# m2_old.net
KiCad netlist of a schematic drawn in EAGLE
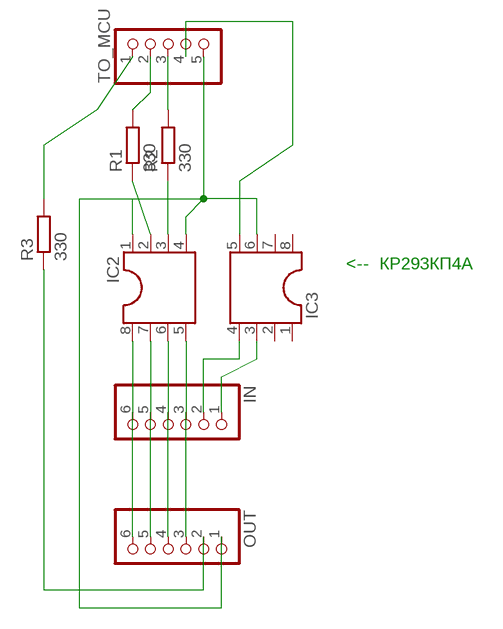
[diagram p0: schematic, sheet 1]

(export (version "E")
  (design (tool "Eeschema 10.0.6"))
  (components
    (comp (ref "IC2")
      (value "DIL8")
      (footprint "eagle-import:DIL08")
      (libsource (lib "eagle-import") (part "DIL8"))
    )
    (comp (ref "IC3")
      (value "DIL8")
      (footprint "eagle-import:DIL08")
      (libsource (lib "eagle-import") (part "DIL8"))
    )
    (comp (ref "IN")
      (value "PINHD-1X6")
      (footprint "eagle-import:1X06")
      (libsource (lib "eagle-import") (part "PINHD-1X6"))
    )
    (comp (ref "OUT")
      (value "PINHD-1X6")
      (footprint "eagle-import:1X06")
      (libsource (lib "eagle-import") (part "PINHD-1X6"))
    )
    (comp (ref "R1")
      (value "330")
      (footprint "eagle-import:0204_5")
      (libsource (lib "eagle-import") (part "R-EU_0204/5"))
    )
    (comp (ref "R2")
      (value "330")
      (footprint "eagle-import:0204_5")
      (libsource (lib "eagle-import") (part "R-EU_0204/5"))
    )
    (comp (ref "R3")
      (value "330")
      (footprint "eagle-import:0204_5")
      (libsource (lib "eagle-import") (part "R-EU_0204/5"))
    )
    (comp (ref "TO_MCU")
      (value "PINHD-1X5")
      (footprint "eagle-import:1X05")
      (libsource (lib "eagle-import") (part "PINHD-1X5"))
    )
  )
  (nets
    (net (code "1") (name "Net-(IC2-Pad1)") (class "Default")
      (node (ref "IC2") (pin "1") (pinfunction "1_1") (pintype "passive"))
      (node (ref "IC2") (pin "4") (pinfunction "4_4") (pintype "passive"))
      (node (ref "IC3") (pin "6") (pinfunction "6_6") (pintype "passive"))
      (node (ref "OUT") (pin "1") (pinfunction "1_1") (pintype "passive"))
      (node (ref "TO_MCU") (pin "5") (pinfunction "5_5") (pintype "passive"))
    )
    (net (code "2") (name "Net-(IC2-Pad2)") (class "Default")
      (node (ref "IC2") (pin "2") (pinfunction "2_2") (pintype "passive"))
      (node (ref "R1") (pin "1") (pinfunction "1_1") (pintype "passive"))
    )
    (net (code "3") (name "Net-(IC2-Pad3)") (class "Default")
      (node (ref "IC2") (pin "3") (pinfunction "3_3") (pintype "passive"))
      (node (ref "R2") (pin "1") (pinfunction "1_1") (pintype "passive"))
    )
    (net (code "4") (name "Net-(IC2-Pad5)") (class "Default")
      (node (ref "IC2") (pin "5") (pinfunction "5_5") (pintype "passive"))
      (node (ref "IN") (pin "3") (pinfunction "3_3") (pintype "passive"))
      (node (ref "OUT") (pin "3") (pinfunction "3_3") (pintype "passive"))
    )
    (net (code "5") (name "Net-(IC2-Pad6)") (class "Default")
      (node (ref "IC2") (pin "6") (pinfunction "6_6") (pintype "passive"))
      (node (ref "IN") (pin "4") (pinfunction "4_4") (pintype "passive"))
      (node (ref "OUT") (pin "4") (pinfunction "4_4") (pintype "passive"))
    )
    (net (code "6") (name "Net-(IC2-Pad7)") (class "Default")
      (node (ref "IC2") (pin "7") (pinfunction "7_7") (pintype "passive"))
      (node (ref "IN") (pin "5") (pinfunction "5_5") (pintype "passive"))
      (node (ref "OUT") (pin "5") (pinfunction "5_5") (pintype "passive"))
    )
    (net (code "7") (name "Net-(IC2-Pad8)") (class "Default")
      (node (ref "IC2") (pin "8") (pinfunction "8_8") (pintype "passive"))
      (node (ref "IN") (pin "6") (pinfunction "6_6") (pintype "passive"))
      (node (ref "OUT") (pin "6") (pinfunction "6_6") (pintype "passive"))
    )
    (net (code "8") (name "Net-(IC3-Pad3)") (class "Default")
      (node (ref "IC3") (pin "3") (pinfunction "3_3") (pintype "passive"))
      (node (ref "IN") (pin "1") (pinfunction "1_1") (pintype "passive"))
    )
    (net (code "9") (name "Net-(IC3-Pad4)") (class "Default")
      (node (ref "IC3") (pin "4") (pinfunction "4_4") (pintype "passive"))
      (node (ref "IN") (pin "2") (pinfunction "2_2") (pintype "passive"))
    )
    (net (code "10") (name "Net-(IC3-Pad5)") (class "Default")
      (node (ref "IC3") (pin "5") (pinfunction "5_5") (pintype "passive"))
      (node (ref "TO_MCU") (pin "4") (pinfunction "4_4") (pintype "passive"))
    )
    (net (code "11") (name "Net-(OUT-Pad2)") (class "Default")
      (node (ref "OUT") (pin "2") (pinfunction "2_2") (pintype "passive"))
      (node (ref "R3") (pin "1") (pinfunction "1_1") (pintype "passive"))
    )
    (net (code "12") (name "Net-(R1-Pad2)") (class "Default")
      (node (ref "R1") (pin "2") (pinfunction "2_2") (pintype "passive"))
      (node (ref "TO_MCU") (pin "2") (pinfunction "2_2") (pintype "passive"))
    )
    (net (code "13") (name "Net-(R2-Pad2)") (class "Default")
      (node (ref "R2") (pin "2") (pinfunction "2_2") (pintype "passive"))
      (node (ref "TO_MCU") (pin "3") (pinfunction "3_3") (pintype "passive"))
    )
    (net (code "14") (name "Net-(R3-Pad2)") (class "Default")
      (node (ref "R3") (pin "2") (pinfunction "2_2") (pintype "passive"))
      (node (ref "TO_MCU") (pin "1") (pinfunction "1_1") (pintype "passive"))
    )
    (net (code "15") (name "unconnected-(IC3-Pad1)") (class "Default")
      (node (ref "IC3") (pin "1") (pinfunction "1_1") (pintype "passive"))
    )
    (net (code "16") (name "unconnected-(IC3-Pad2)") (class "Default")
      (node (ref "IC3") (pin "2") (pinfunction "2_2") (pintype "passive"))
    )
    (net (code "17") (name "unconnected-(IC3-Pad7)") (class "Default")
      (node (ref "IC3") (pin "7") (pinfunction "7_7") (pintype "passive"))
    )
    (net (code "18") (name "unconnected-(IC3-Pad8)") (class "Default")
      (node (ref "IC3") (pin "8") (pinfunction "8_8") (pintype "passive"))
    )
  )
)
